# RF_frontend.net
KiCad netlist of a schematic drawn in Altium Designer
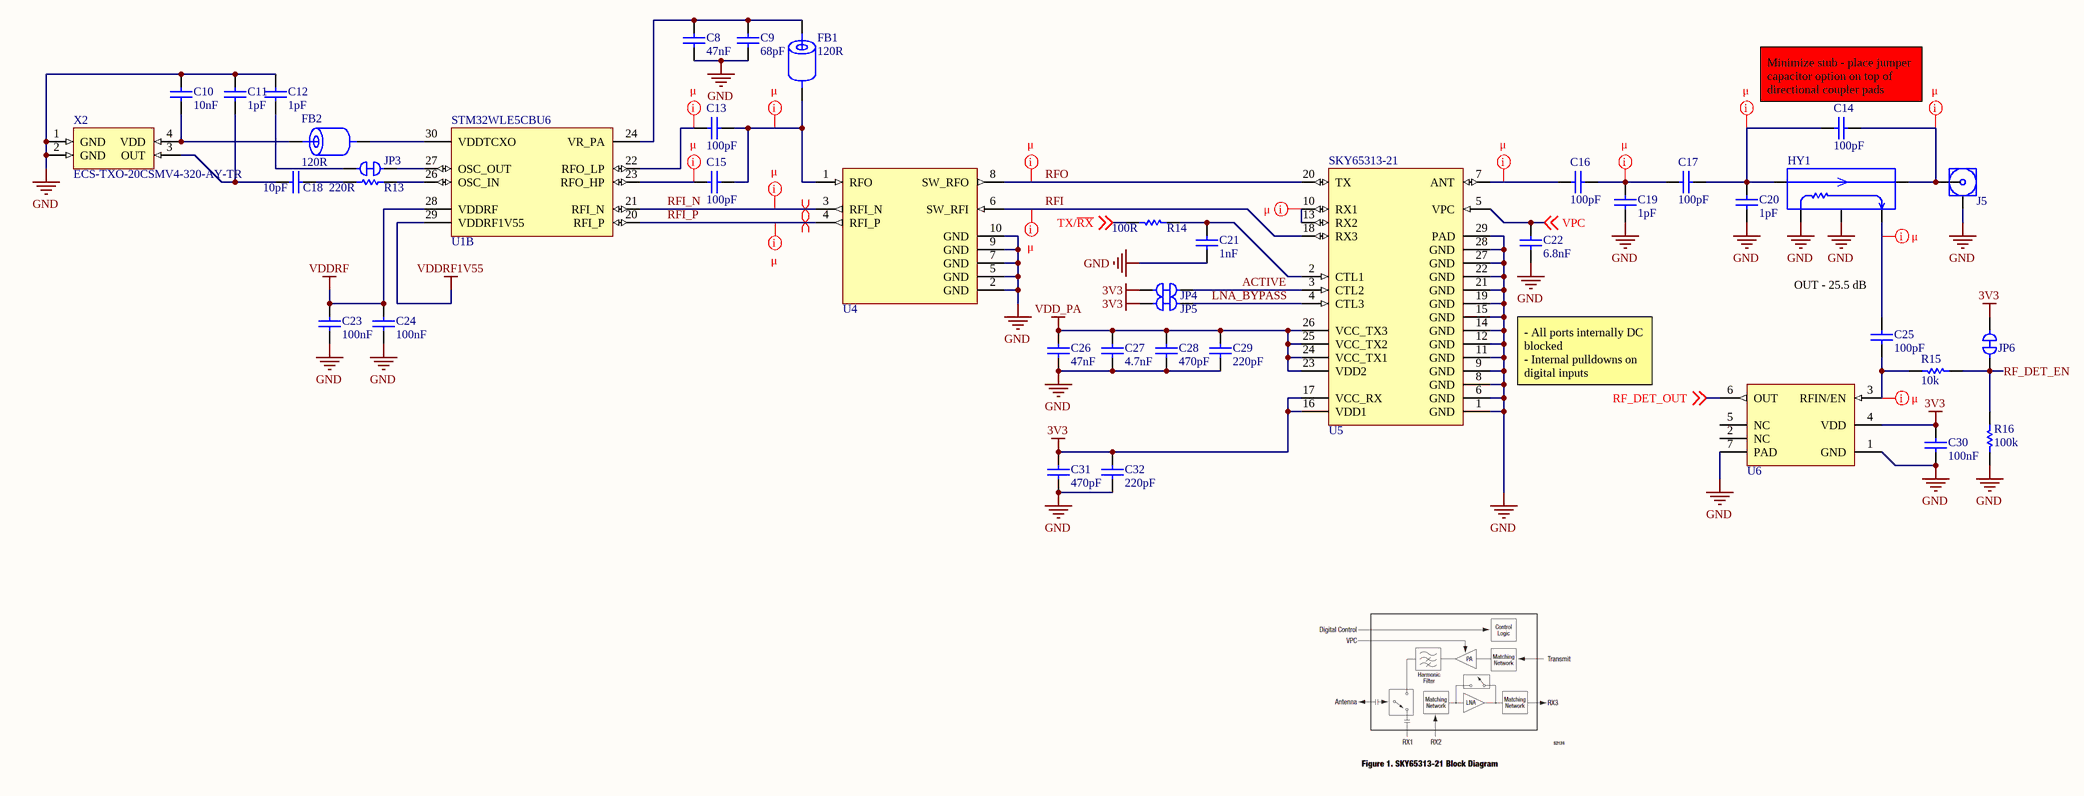
[diagram p0: RF frontend.SchDoc]

(export (version "E")
  (design (tool "Eeschema 10.0.6"))
  (components
    (comp (ref "C8")
      (value "47nF")
      (footprint "CAPC1608X10N")
      (description "Prices include import duty and tax. CAP, 0.047UF, 50V, MLCC, 0603; SVHC: No SVHC (15-Jan-2019)")
      (fields (field (name "VOLTAGE") "50V") (field (name "TOLERANCE") "10%"))
      (libsource (lib "UWA Aerospace") (part "C0603C104M5RACTU"))
    )
    (comp (ref "C9")
      (value "68pF")
      (footprint "CAPC1005X06N")
      (description "Ceramic capacitor SMD-0402 68pF /50V C0G# J +-5%, Samsung, RoHS")
      (fields (field (name "VOLTAGE") "50V") (field (name "TOLERANCE") "5%"))
      (libsource (lib "UWA Aerospace") (part "Capacitor - Non-polar"))
    )
    (comp (ref "C10")
      (value "10nF")
      (footprint "CAPC1608X10N")
      (description "Cap Ceramic 0.01uF 50V X7R 5% SMD 0603 125C Paper T/R")
      (fields (field (name "TOLERANCE") "5%") (field (name "Comment") "C0603C103J5RACTU"))
      (libsource (lib "UWA Aerospace") (part "C0603C104M5RACTU"))
    )
    (comp (ref "C11")
      (value "1pF")
      (footprint "CAPC1608X10N")
      (description "0603 1 pF 100 V ±0.25 pF Tolerance NP0 SMT Multilayer Ceramic Capacitor")
      (fields (field (name "Comment") "CC0603CRNPO0BN1R0"))
      (libsource (lib "UWA Aerospace") (part "Capacitor - Non-polar"))
    )
    (comp (ref "C12")
      (value "1pF")
      (footprint "CAPC1608X10N")
      (description "0603 1 pF 100 V ±0.25 pF Tolerance NP0 SMT Multilayer Ceramic Capacitor")
      (fields (field (name "Comment") "CC0603CRNPO0BN1R0"))
      (libsource (lib "UWA Aerospace") (part "Capacitor - Non-polar"))
    )
    (comp (ref "C13")
      (value "100pF")
      (footprint "CAPC1005X05N")
      (description "Cap Ceramic 100pF 50V C0G 5% SMD 0402 125C Paper T/R")
      (fields (field (name "Comment") "C0402C101J5GAC7411"))
      (libsource (lib "UWA Aerospace") (part "C0603C104M5RACTU"))
    )
    (comp (ref "C14")
      (value "100pF")
      (footprint "CAPC1005X05N")
      (description "Cap Ceramic 100pF 50V C0G 5% SMD 0402 125C Paper T/R")
      (fields (field (name "Comment") "C0402C101J5GAC7411"))
      (libsource (lib "UWA Aerospace") (part "C0603C104M5RACTU"))
    )
    (comp (ref "C15")
      (value "100pF")
      (footprint "CAPC1005X05N")
      (description "Cap Ceramic 100pF 50V C0G 5% SMD 0402 125C Paper T/R")
      (fields (field (name "Comment") "C0402C101J5GAC7411"))
      (libsource (lib "UWA Aerospace") (part "C0603C104M5RACTU"))
    )
    (comp (ref "C16")
      (value "100pF")
      (footprint "CAPC1005X05N")
      (description "Cap Ceramic 100pF 50V C0G 5% SMD 0402 125C Paper T/R")
      (fields (field (name "Comment") "C0402C101J5GAC7411"))
      (libsource (lib "UWA Aerospace") (part "C0603C104M5RACTU"))
    )
    (comp (ref "C17")
      (value "100pF")
      (footprint "CAPC1005X05N")
      (description "Cap Ceramic 100pF 50V C0G 5% SMD 0402 125C Paper T/R")
      (fields (field (name "Comment") "C0402C101J5GAC7411"))
      (libsource (lib "UWA Aerospace") (part "C0603C104M5RACTU"))
    )
    (comp (ref "C18")
      (value "10pF")
      (footprint "CAPC1608X10N")
      (description "0603 10pF 50V ±5 % Tolerance C0G SMT Multilayer Ceramic Capacitor")
      (fields (field (name "TOLERANCE") "5%") (field (name "VOLTAGE") "50V"))
      (libsource (lib "UWA Aerospace") (part "Capacitor - Non-polar"))
    )
    (comp (ref "C19")
      (value "1pF")
      (footprint "CAPC1005X05N")
      (description "Cap Ceramic 1pF 50V C0G 5% Pad SMD 0402 125C Automotive T/R")
      (fields (field (name "Comment") "GCM1555C1H1R0JA16D"))
      (libsource (lib "UWA Aerospace") (part "C0603C104M5RACTU"))
    )
    (comp (ref "C20")
      (value "1pF")
      (footprint "CAPC1005X05N")
      (description "Cap Ceramic 1pF 50V C0G 5% Pad SMD 0402 125C Automotive T/R")
      (fields (field (name "Comment") "GCM1555C1H1R0JA16D"))
      (libsource (lib "UWA Aerospace") (part "C0603C104M5RACTU"))
    )
    (comp (ref "C21")
      (value "1nF")
      (footprint "CAPC1608X10N")
      (description "Cap Ceramic 0.001uF 50V X7R 10% SMD 0603 125°C Bulk")
      (fields (field (name "TOLERANCE") "10%") (field (name "VOLTAGE") "50V"))
      (libsource (lib "UWA Aerospace") (part "Capacitor - Non-polar"))
    )
    (comp (ref "C22")
      (value "6.8nF")
      (footprint "CAPC1005X06N")
      (description "50V 6.8nF X7R ±10% 0402 Multilayer Ceramic Capacitors MLCC - SMD/SMT ROHS")
      (fields (field (name "Comment") "0402B682K500NT"))
      (libsource (lib "UWA Aerospace") (part "Capacitor - Non-polar"))
    )
    (comp (ref "C23")
      (value "100nF")
      (footprint "CAPC1608X10N")
      (description "Cap Ceramic 0.1uF 50V X7R 20% SMD 0603 125C T/R")
      (fields (field (name "TOLERANCE") "20%") (field (name "Comment") "C0603C104M5RACTU"))
      (libsource (lib "UWA Aerospace") (part "C0603C104M5RACTU"))
    )
    (comp (ref "C24")
      (value "100nF")
      (footprint "CAPC1608X10N")
      (description "Cap Ceramic 0.1uF 50V X7R 20% SMD 0603 125C T/R")
      (fields (field (name "TOLERANCE") "20%") (field (name "Comment") "C0603C104M5RACTU"))
      (libsource (lib "UWA Aerospace") (part "C0603C104M5RACTU"))
    )
    (comp (ref "C25")
      (value "100pF")
      (footprint "CAPC1005X05N")
      (description "Cap Ceramic 100pF 50V C0G 5% SMD 0402 125C Paper T/R")
      (fields (field (name "Comment") "C0402C101J5GAC7411"))
      (libsource (lib "UWA Aerospace") (part "C0603C104M5RACTU"))
    )
    (comp (ref "C26")
      (value "47nF")
      (footprint "CAPC1608X10N")
      (description "Prices include import duty and tax. CAP, 0.047UF, 50V, MLCC, 0603; SVHC: No SVHC (15-Jan-2019)")
      (fields (field (name "VOLTAGE") "50V") (field (name "TOLERANCE") "10%"))
      (libsource (lib "UWA Aerospace") (part "C0603C104M5RACTU"))
    )
    (comp (ref "C27")
      (value "4.7nF")
      (footprint "CAPC1608X10N")
      (description "50V 4.7nF X7R ±10% 0603  Multilayer Ceramic Capacitors MLCC - SMD/SMT ROHS")
      (fields (field (name "Comment") "0603B472K500NT"))
      (libsource (lib "UWA Aerospace") (part "Capacitor - Non-polar"))
    )
    (comp (ref "C28")
      (value "470pF")
      (footprint "CAPC1608X10N")
      (description "Cap Ceramic 470pF 100V X7R 5% SMD 0603 125°C Paper T/R")
      (fields (field (name "TOLERANCE") "5%") (field (name "Comment") "C0603C471J1RACTU"))
      (libsource (lib "UWA Aerospace") (part "Capacitor - Non-polar"))
    )
    (comp (ref "C29")
      (value "220pF")
      (footprint "CAPC1608X10N")
      (description "CAP CER 220PF 50V X7R 0603")
      (fields (field (name "TOLERANCE") "10%") (field (name "VOLTAGE") "50V"))
      (libsource (lib "UWA Aerospace") (part "Capacitor - Non-polar"))
    )
    (comp (ref "C30")
      (value "100nF")
      (footprint "CAPC1608X10N")
      (description "Cap Ceramic 0.1uF 50V X7R 20% SMD 0603 125C T/R")
      (fields (field (name "TOLERANCE") "20%") (field (name "Comment") "C0603C104M5RACTU"))
      (libsource (lib "UWA Aerospace") (part "C0603C104M5RACTU"))
    )
    (comp (ref "C31")
      (value "470pF")
      (footprint "CAPC1608X10N")
      (description "Cap Ceramic 470pF 100V X7R 5% SMD 0603 125°C Paper T/R")
      (fields (field (name "TOLERANCE") "5%") (field (name "Comment") "C0603C471J1RACTU"))
      (libsource (lib "UWA Aerospace") (part "Capacitor - Non-polar"))
    )
    (comp (ref "C32")
      (value "220pF")
      (footprint "CAPC1608X10N")
      (description "CAP CER 220PF 50V X7R 0603")
      (fields (field (name "TOLERANCE") "10%") (field (name "VOLTAGE") "50V"))
      (libsource (lib "UWA Aerospace") (part "Capacitor - Non-polar"))
    )
    (comp (ref "FB1")
      (value "120R")
      (footprint "INDC1608X10N")
      (description "Ferrite Beads Multi-Layer High Current 120Ohm 25% 100MHz 2A 0.05Ohm DCR 0603 T/R")
      (fields (field (name "Comment") "PE-0603PFB121ST"))
      (libsource (lib "") (part "Ferrite Bead_1"))
    )
    (comp (ref "FB2")
      (value "120R")
      (footprint "INDC1608X10N")
      (description "Ferrite Beads Multi-Layer High Current 120Ohm 25% 100MHz 2A 0.05Ohm DCR 0603 T/R")
      (fields (field (name "Comment") "PE-0603PFB121ST"))
      (libsource (lib "UWA Aerospace") (part "Ferrite Bead"))
    )
    (comp (ref "HY1")
      (value "HHM22139A2")
      (footprint "SOTFL55P150X70-6N")
      (description "Multilayer Directional Coupler for 698MHz to 2620MHz 6-Pin SMD")
      (libsource (lib "UWA Aerospace") (part "Directional coupler - internally isolated"))
    )
    (comp (ref "J5")
      (value "EMPCB.SMAFSTJ.B.HT")
      (footprint "FP-EMPCB_SMAFSTJ_B_HT-MFG")
      (description "SMA Connector Jack, Female Socket 50 Ohm Board Edge, End Launch Solder")
      (libsource (lib "UWA Aerospace") (part "Connector - Coaxial"))
    )
    (comp (ref "JP3")
      (value "RC0603FR-070RL")
      (footprint "RESC1608X05N")
      (description "RC Series 0603 0.1 W 0 Ohm Jumper Surface Mount Thick Film Chip Resistor")
      (fields (field (name "TOLERANCE") "1%"))
      (libsource (lib "") (part "Jumper - Closed_1"))
    )
    (comp (ref "JP4")
      (value "RC0603FR-070RL")
      (footprint "RESC1608X05N")
      (description "RC Series 0603 0.1 W 0 Ohm Jumper Surface Mount Thick Film Chip Resistor")
      (fields (field (name "TOLERANCE") "1%"))
      (libsource (lib "UWA Aerospace") (part "Jumper - Closed"))
    )
    (comp (ref "JP5")
      (value "RC0603FR-070RL")
      (footprint "RESC1608X05N")
      (description "RC Series 0603 0.1 W 0 Ohm Jumper Surface Mount Thick Film Chip Resistor")
      (fields (field (name "TOLERANCE") "1%"))
      (libsource (lib "UWA Aerospace") (part "Jumper - Closed"))
    )
    (comp (ref "JP6")
      (value "RC0603FR-070RL")
      (footprint "RESC1608X05N")
      (description "RC Series 0603 0.1 W 0 Ohm Jumper Surface Mount Thick Film Chip Resistor")
      (fields (field (name "TOLERANCE") "1%"))
      (libsource (lib "UWA Aerospace") (part "Jumper - Closed"))
    )
    (comp (ref "R13")
      (value "220R")
      (footprint "RESC1005X04N")
      (description "Res Thick Film 0402 220 Ohm 5% 1/16W ±100ppm/°C Molded SMD SMD Paper T/R")
      (fields (field (name "TOLERANCE") "5%") (field (name "Comment") "0402WGF2200TCE"))
      (libsource (lib "UWA Aerospace") (part "Resistor"))
    )
    (comp (ref "R14")
      (value "100R")
      (footprint "RESC1608X06N")
      (description "RES SMD 100 OHM 1% 1/10W 0603")
      (fields (field (name "TOLERANCE") "1%") (field (name "Comment") "CRCW0603100RFKEAC"))
      (libsource (lib "UWA Aerospace") (part "WSLP1206R0500FEA"))
    )
    (comp (ref "R15")
      (value "10k")
      (footprint "RESC1608X06N")
      (fields (field (name "TOLERANCE") "1%") (field (name "Comment") "CRCW060310K0FKEA"))
      (libsource (lib "UWA Aerospace") (part "CRCW060310K0FKEA"))
    )
    (comp (ref "R16")
      (value "100k")
      (footprint "RESC1608X05N")
      (description "RES SMD 100K OHM 1% 1/10W 0603")
      (fields (field (name "TOLERANCE") "1%") (field (name "Comment") "RC0603FR-07100KL"))
      (libsource (lib "UWA Aerospace") (part "Resistor"))
    )
    (comp (ref "U1")
      (value "STM32WLE5CBU6")
      (footprint "QFN50P700X700X60_HS-49L")
      (description "Microcontroller 32-Bit Arm Cortex-M4 RISC 128Kbyte 1.8V to 3.6V 48-Pin UFQFPN Industrial")
      (libsource (lib "UWA Aerospace") (part "STM32WLE5CBU6-Symbol-1"))
    )
    (comp (ref "U4")
      (value "0900FM15K0039001E")
      (footprint "0900FM15K0039001E-Footprint-1")
      (description "Semtech SX1261 SX1262 Balun Filt")
      (libsource (lib "UWA Aerospace") (part "0900FM15K0039001E-Symbol-1"))
    )
    (comp (ref "U5")
      (value "SKY65313-21")
      (footprint "QFN75P600X600X100_HS-25N")
      (description "Skyworks 900 MHz front end module 30.5 dBm")
      (libsource (lib "UWA Aerospace") (part "SKY65313-21"))
    )
    (comp (ref "U6")
      (value "LMV228SD/NOPB")
      (footprint "NGF0006A_V")
      (description "RF Detector 450MHz to 2000MHz 15dBm 6-Pin WSON EP T/R")
      (libsource (lib "UWA Aerospace") (part "RF-PWD-LMV22X-6"))
    )
    (comp (ref "X2")
      (value "ECS-TXO-20CSMV4-320-AY-TR")
      (footprint "ECS-TXO-20CSMV4-320-AY-TR-Footprint-1")
      (description "Xtal Osc Tcxo 32.0000MHZ Clpsw 10 pF 0.5 ppm")
      (libsource (lib "UWA Aerospace") (part "ECS-TXO-20CSMV4-320-AY-TR-Symbol-1"))
    )
  )
  (nets
    (net (code "1") (name "/ACTIVE") (class "Default")
      (node (ref "JP4") (pin "2") (pinfunction "2_2") (pintype "passive"))
      (node (ref "U5") (pin "3") (pinfunction "CTL2_3") (pintype "input"))
    )
    (net (code "2") (name "/LNA_BYPASS") (class "Default")
      (node (ref "JP5") (pin "2") (pinfunction "2_2") (pintype "passive"))
      (node (ref "U5") (pin "4") (pinfunction "CTL3_4") (pintype "input"))
    )
    (net (code "3") (name "/RFI") (class "Default")
      (node (ref "U4") (pin "6") (pinfunction "SW_RFI_6") (pintype "input"))
      (node (ref "U5") (pin "18") (pinfunction "RX3_18") (pintype "bidirectional"))
    )
    (net (code "4") (name "/RFI_N") (class "Default")
      (node (ref "U1") (pin "21") (pinfunction "RFI_N_21") (pintype "bidirectional"))
      (node (ref "U4") (pin "3") (pinfunction "RFI_N_3") (pintype "output"))
    )
    (net (code "5") (name "/RFI_P") (class "Default")
      (node (ref "U1") (pin "20") (pinfunction "RFI_P_20") (pintype "bidirectional"))
      (node (ref "U4") (pin "4") (pinfunction "RFI_P_4") (pintype "output"))
    )
    (net (code "6") (name "/RFO") (class "Default")
      (node (ref "U4") (pin "8") (pinfunction "SW_RFO_8") (pintype "output"))
      (node (ref "U5") (pin "20") (pinfunction "TX_20") (pintype "bidirectional"))
    )
    (net (code "7") (name "/RF_DET_EN") (class "Default")
      (node (ref "JP6") (pin "1") (pinfunction "1_1") (pintype "passive"))
      (node (ref "R15") (pin "2") (pinfunction "2_2") (pintype "passive"))
      (node (ref "R16") (pin "2") (pinfunction "2_2") (pintype "passive"))
    )
    (net (code "8") (name "3V3") (class "Default")
      (node (ref "C30") (pin "2") (pinfunction "2_2") (pintype "passive"))
      (node (ref "C31") (pin "2") (pinfunction "2_2") (pintype "passive"))
      (node (ref "C32") (pin "2") (pinfunction "2_2") (pintype "passive"))
      (node (ref "JP4") (pin "1") (pinfunction "1_1") (pintype "passive"))
      (node (ref "JP5") (pin "1") (pinfunction "1_1") (pintype "passive"))
      (node (ref "JP6") (pin "2") (pinfunction "2_2") (pintype "passive"))
      (node (ref "U5") (pin "16") (pinfunction "VDD1_16") (pintype "power_in"))
      (node (ref "U5") (pin "17") (pinfunction "VCC_RX_17") (pintype "power_in"))
      (node (ref "U6") (pin "4") (pinfunction "VDD_4") (pintype "power_in"))
    )
    (net (code "9") (name "GND") (class "Default")
      (node (ref "C10") (pin "2") (pinfunction "2_2") (pintype "passive"))
      (node (ref "C11") (pin "1") (pinfunction "1_1") (pintype "passive"))
      (node (ref "C12") (pin "1") (pinfunction "1_1") (pintype "passive"))
      (node (ref "C19") (pin "1") (pinfunction "1_1") (pintype "passive"))
      (node (ref "C20") (pin "1") (pinfunction "1_1") (pintype "passive"))
      (node (ref "C21") (pin "1") (pinfunction "1_1") (pintype "passive"))
      (node (ref "C22") (pin "1") (pinfunction "1_1") (pintype "passive"))
      (node (ref "C23") (pin "1") (pinfunction "1_1") (pintype "passive"))
      (node (ref "C24") (pin "1") (pinfunction "1_1") (pintype "passive"))
      (node (ref "C26") (pin "2") (pinfunction "2_2") (pintype "passive"))
      (node (ref "C27") (pin "2") (pinfunction "2_2") (pintype "passive"))
      (node (ref "C28") (pin "2") (pinfunction "2_2") (pintype "passive"))
      (node (ref "C29") (pin "2") (pinfunction "2_2") (pintype "passive"))
      (node (ref "C30") (pin "1") (pinfunction "1_1") (pintype "passive"))
      (node (ref "C31") (pin "1") (pinfunction "1_1") (pintype "passive"))
      (node (ref "C32") (pin "1") (pinfunction "1_1") (pintype "passive"))
      (node (ref "C8") (pin "1") (pinfunction "1_1") (pintype "passive"))
      (node (ref "C9") (pin "1") (pinfunction "1_1") (pintype "passive"))
      (node (ref "HY1") (pin "4") (pinfunction "ISOLATED_4") (pintype "passive"))
      (node (ref "HY1") (pin "5") (pinfunction "GND_5") (pintype "passive"))
      (node (ref "J5") (pin "2") (pinfunction "GND_2") (pintype "passive"))
      (node (ref "R16") (pin "1") (pinfunction "1_1") (pintype "passive"))
      (node (ref "U4") (pin "10") (pinfunction "GND_10") (pintype "passive"))
      (node (ref "U4") (pin "2") (pinfunction "GND_2") (pintype "passive"))
      (node (ref "U4") (pin "5") (pinfunction "GND_5") (pintype "passive"))
      (node (ref "U4") (pin "7") (pinfunction "GND_7") (pintype "passive"))
      (node (ref "U4") (pin "9") (pinfunction "GND_9") (pintype "passive"))
      (node (ref "U5") (pin "1") (pinfunction "GND_1") (pintype "power_in"))
      (node (ref "U5") (pin "11") (pinfunction "GND_11") (pintype "power_in"))
      (node (ref "U5") (pin "12") (pinfunction "GND_12") (pintype "power_in"))
      (node (ref "U5") (pin "14") (pinfunction "GND_14") (pintype "power_in"))
      (node (ref "U5") (pin "15") (pinfunction "GND_15") (pintype "power_in"))
      (node (ref "U5") (pin "19") (pinfunction "GND_19") (pintype "power_in"))
      (node (ref "U5") (pin "21") (pinfunction "GND_21") (pintype "power_in"))
      (node (ref "U5") (pin "22") (pinfunction "GND_22") (pintype "power_in"))
      (node (ref "U5") (pin "27") (pinfunction "GND_27") (pintype "power_in"))
      (node (ref "U5") (pin "28") (pinfunction "GND_28") (pintype "power_in"))
      (node (ref "U5") (pin "29") (pinfunction "PAD_29") (pintype "passive"))
      (node (ref "U5") (pin "6") (pinfunction "GND_6") (pintype "power_in"))
      (node (ref "U5") (pin "8") (pinfunction "GND_8") (pintype "power_in"))
      (node (ref "U5") (pin "9") (pinfunction "GND_9") (pintype "power_in"))
      (node (ref "U6") (pin "1") (pinfunction "GND_1") (pintype "power_in"))
      (node (ref "U6") (pin "7") (pinfunction "PAD_7") (pintype "power_in"))
      (node (ref "X2") (pin "1") (pinfunction "GND_1") (pintype "input"))
      (node (ref "X2") (pin "2") (pinfunction "GND_2") (pintype "input"))
    )
    (net (code "10") (name "Net-(C12-Pad2)") (class "Default")
      (node (ref "C12") (pin "2") (pinfunction "2_2") (pintype "passive"))
      (node (ref "JP3") (pin "2") (pinfunction "2_2") (pintype "passive"))
    )
    (net (code "11") (name "Net-(C16-Pad1)") (class "Default")
      (node (ref "C16") (pin "1") (pinfunction "1_1") (pintype "passive"))
      (node (ref "C17") (pin "2") (pinfunction "2_2") (pintype "passive"))
      (node (ref "C19") (pin "2") (pinfunction "2_2") (pintype "passive"))
    )
    (net (code "12") (name "Net-(C18-Pad2)") (class "Default")
      (node (ref "C18") (pin "2") (pinfunction "2_2") (pintype "passive"))
      (node (ref "R13") (pin "2") (pinfunction "2_2") (pintype "passive"))
    )
    (net (code "13") (name "Net-(HY1-COUPLED)") (class "Default")
      (node (ref "C25") (pin "1") (pinfunction "1_1") (pintype "passive"))
      (node (ref "HY1") (pin "3") (pinfunction "COUPLED_3") (pintype "passive"))
    )
    (net (code "14") (name "Net-(HY1-INPUT)") (class "Default")
      (node (ref "C14") (pin "2") (pinfunction "2_2") (pintype "passive"))
      (node (ref "C17") (pin "1") (pinfunction "1_1") (pintype "passive"))
      (node (ref "C20") (pin "2") (pinfunction "2_2") (pintype "passive"))
      (node (ref "HY1") (pin "1") (pinfunction "INPUT_1") (pintype "passive"))
    )
    (net (code "15") (name "Net-(HY1-TRANSMITTED)") (class "Default")
      (node (ref "C14") (pin "1") (pinfunction "1_1") (pintype "passive"))
      (node (ref "HY1") (pin "2") (pinfunction "TRANSMITTED_2") (pintype "passive"))
      (node (ref "J5") (pin "1") (pinfunction "SIG_1") (pintype "passive"))
    )
    (net (code "16") (name "Net-(U1B-OSC_IN)") (class "Default")
      (node (ref "R13") (pin "1") (pinfunction "1_1") (pintype "passive"))
      (node (ref "U1") (pin "26") (pinfunction "OSC_IN_26") (pintype "bidirectional"))
    )
    (net (code "17") (name "Net-(U1B-OSC_OUT)") (class "Default")
      (node (ref "JP3") (pin "1") (pinfunction "1_1") (pintype "passive"))
      (node (ref "U1") (pin "27") (pinfunction "OSC_OUT_27") (pintype "bidirectional"))
    )
    (net (code "18") (name "Net-(U1B-RFO_HP)") (class "Default")
      (node (ref "C15") (pin "2") (pinfunction "2_2") (pintype "passive"))
      (node (ref "U1") (pin "23") (pinfunction "RFO_HP_23") (pintype "bidirectional"))
    )
    (net (code "19") (name "Net-(U1B-RFO_LP)") (class "Default")
      (node (ref "C13") (pin "2") (pinfunction "2_2") (pintype "passive"))
      (node (ref "U1") (pin "22") (pinfunction "RFO_LP_22") (pintype "bidirectional"))
    )
    (net (code "20") (name "Net-(U1B-VDDTCXO)") (class "Default")
      (node (ref "FB2") (pin "2") (pinfunction "2_2") (pintype "passive"))
      (node (ref "U1") (pin "30") (pinfunction "VDDTCXO_30") (pintype "power_in"))
    )
    (net (code "21") (name "Net-(U1B-VR_PA)") (class "Default")
      (node (ref "C8") (pin "2") (pinfunction "2_2") (pintype "passive"))
      (node (ref "C9") (pin "2") (pinfunction "2_2") (pintype "passive"))
      (node (ref "FB1") (pin "1") (pinfunction "1_1") (pintype "passive"))
      (node (ref "U1") (pin "24") (pinfunction "VR_PA_24") (pintype "power_in"))
    )
    (net (code "22") (name "Net-(U4-RFO)") (class "Default")
      (node (ref "C13") (pin "1") (pinfunction "1_1") (pintype "passive"))
      (node (ref "C15") (pin "1") (pinfunction "1_1") (pintype "passive"))
      (node (ref "FB1") (pin "2") (pinfunction "2_2") (pintype "passive"))
      (node (ref "U4") (pin "1") (pinfunction "RFO_1") (pintype "input"))
    )
    (net (code "23") (name "Net-(U5-ANT)") (class "Default")
      (node (ref "C16") (pin "2") (pinfunction "2_2") (pintype "passive"))
      (node (ref "U5") (pin "7") (pinfunction "ANT_7") (pintype "bidirectional"))
    )
    (net (code "24") (name "Net-(U5-CTL1)") (class "Default")
      (node (ref "C21") (pin "2") (pinfunction "2_2") (pintype "passive"))
      (node (ref "R14") (pin "2") (pinfunction "2_2") (pintype "passive"))
      (node (ref "U5") (pin "2") (pinfunction "CTL1_2") (pintype "input"))
    )
    (net (code "25") (name "Net-(U5-RX1)") (class "Default")
      (node (ref "U5") (pin "10") (pinfunction "RX1_10") (pintype "bidirectional"))
      (node (ref "U5") (pin "13") (pinfunction "RX2_13") (pintype "bidirectional"))
    )
    (net (code "26") (name "Net-(U6-RFIN{slash}EN)") (class "Default")
      (node (ref "C25") (pin "2") (pinfunction "2_2") (pintype "passive"))
      (node (ref "R15") (pin "1") (pinfunction "1_1") (pintype "passive"))
      (node (ref "U6") (pin "3") (pinfunction "RFIN/EN_3") (pintype "input"))
    )
    (net (code "27") (name "Net-(X2-OUT)") (class "Default")
      (node (ref "C11") (pin "2") (pinfunction "2_2") (pintype "passive"))
      (node (ref "C18") (pin "1") (pinfunction "1_1") (pintype "passive"))
      (node (ref "X2") (pin "3") (pinfunction "OUT_3") (pintype "input"))
    )
    (net (code "28") (name "Net-(X2-VDD)") (class "Default")
      (node (ref "C10") (pin "1") (pinfunction "1_1") (pintype "passive"))
      (node (ref "FB2") (pin "1") (pinfunction "1_1") (pintype "passive"))
      (node (ref "X2") (pin "4") (pinfunction "VDD_4") (pintype "input"))
    )
    (net (code "29") (name "RF_DET_OUT") (class "Default")
      (node (ref "U6") (pin "6") (pinfunction "OUT_6") (pintype "output"))
    )
    (net (code "30") (name "TX{slash}~{RX}") (class "Default")
      (node (ref "R14") (pin "1") (pinfunction "1_1") (pintype "passive"))
    )
    (net (code "31") (name "VDDRF") (class "Default")
      (node (ref "C23") (pin "2") (pinfunction "2_2") (pintype "passive"))
      (node (ref "C24") (pin "2") (pinfunction "2_2") (pintype "passive"))
      (node (ref "U1") (pin "28") (pinfunction "VDDRF_28") (pintype "power_in"))
    )
    (net (code "32") (name "VDDRF1V55") (class "Default")
      (node (ref "U1") (pin "29") (pinfunction "VDDRF1V55_29") (pintype "power_in"))
    )
    (net (code "33") (name "VDD_PA") (class "Default")
      (node (ref "C26") (pin "1") (pinfunction "1_1") (pintype "passive"))
      (node (ref "C27") (pin "1") (pinfunction "1_1") (pintype "passive"))
      (node (ref "C28") (pin "1") (pinfunction "1_1") (pintype "passive"))
      (node (ref "C29") (pin "1") (pinfunction "1_1") (pintype "passive"))
      (node (ref "U5") (pin "23") (pinfunction "VDD2_23") (pintype "power_in"))
      (node (ref "U5") (pin "24") (pinfunction "VCC_TX1_24") (pintype "power_in"))
      (node (ref "U5") (pin "25") (pinfunction "VCC_TX2_25") (pintype "power_in"))
      (node (ref "U5") (pin "26") (pinfunction "VCC_TX3_26") (pintype "power_in"))
    )
    (net (code "34") (name "VPC") (class "Default")
      (node (ref "C22") (pin "2") (pinfunction "2_2") (pintype "passive"))
      (node (ref "U5") (pin "5") (pinfunction "VPC_5") (pintype "input"))
    )
    (net (code "35") (name "unconnected-(U6-NC-Pad2)") (class "Default")
      (node (ref "U6") (pin "2") (pinfunction "NC_2") (pintype "passive"))
    )
    (net (code "36") (name "unconnected-(U6-NC-Pad5)") (class "Default")
      (node (ref "U6") (pin "5") (pinfunction "NC_5") (pintype "passive"))
    )
  )
)
